# Channel_B.net
KiCad netlist of a schematic drawn in Altium Designer
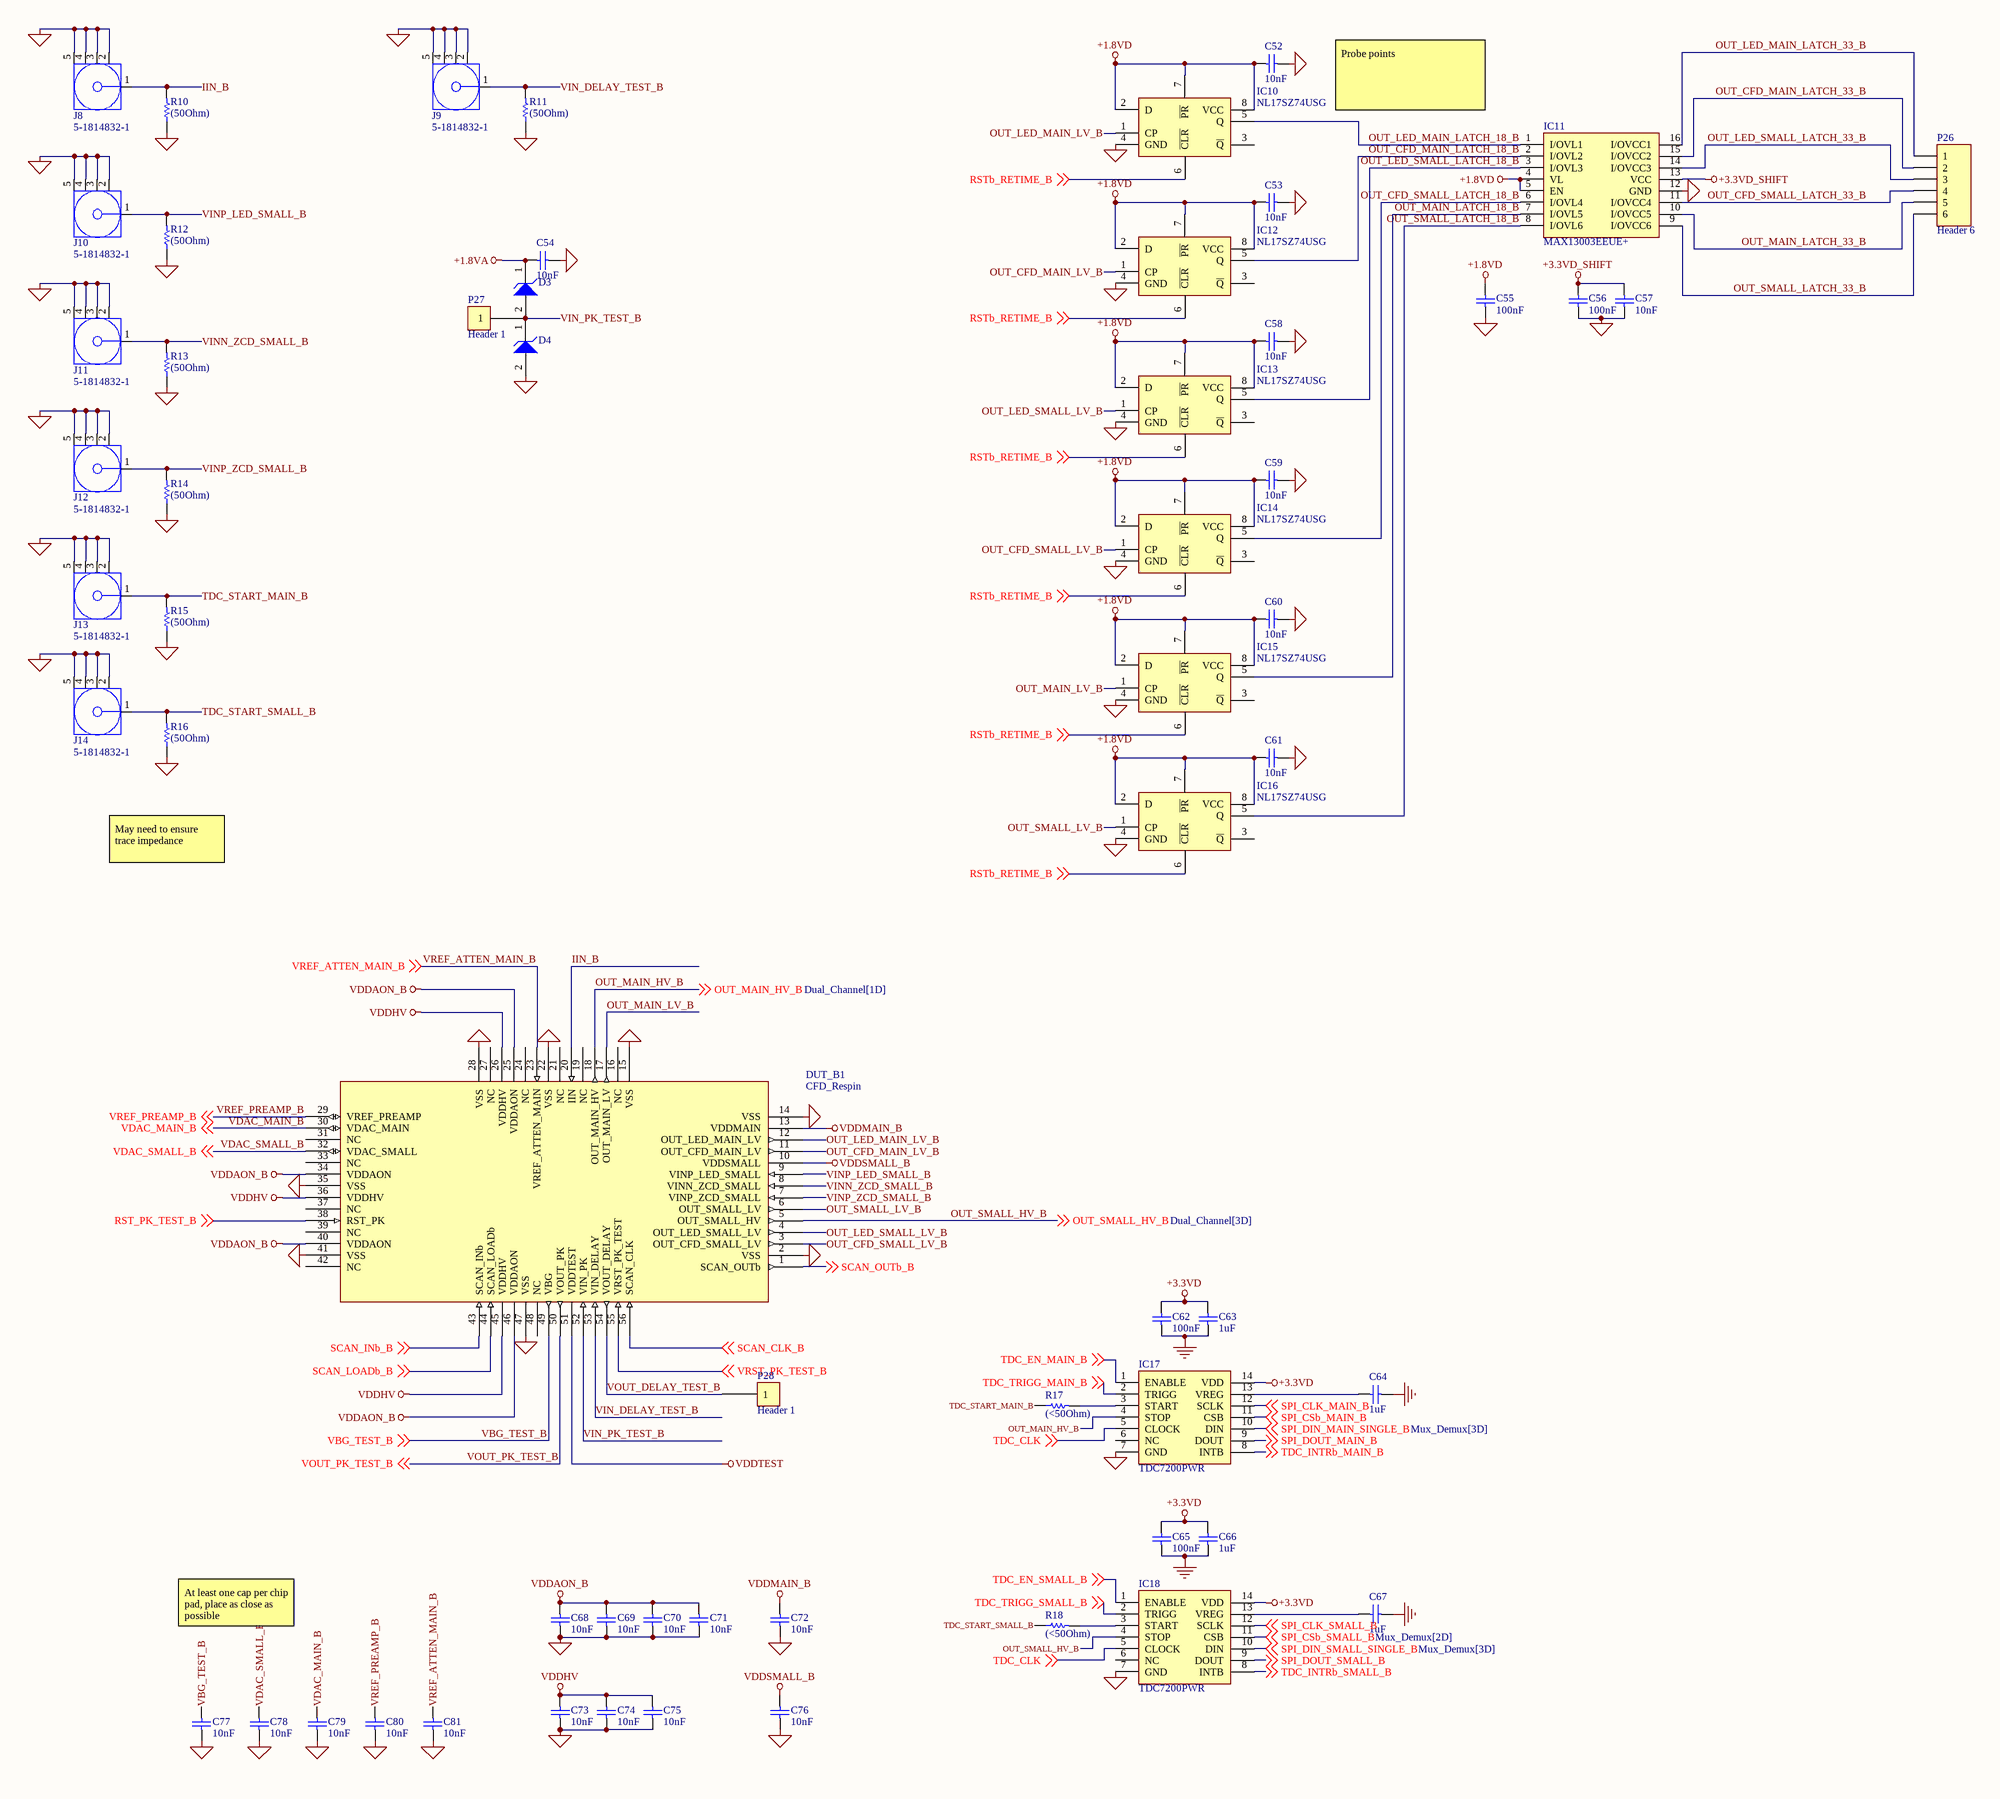
[diagram p0: Channel_B.SchDoc]

(export (version "E")
  (design (tool "Eeschema 10.0.6"))
  (components
    (comp (ref "C52")
      (value "10nF")
      (footprint "CAPC1608X90X35ML10T15")
      (description "0603")
      (fields (field (name "MANUFACTURER") "Murata"))
      (libsource (lib "Altium Content Vault") (part "CAP-NP-2"))
    )
    (comp (ref "C53")
      (value "10nF")
      (footprint "CAPC1608X90X35ML10T15")
      (description "0603")
      (fields (field (name "MANUFACTURER") "Murata"))
      (libsource (lib "Altium Content Vault") (part "CAP-NP-2"))
    )
    (comp (ref "C54")
      (value "10nF")
      (footprint "CAPC1608X90X35ML10T15")
      (description "0603")
      (fields (field (name "MANUFACTURER") "Murata"))
      (libsource (lib "Altium Content Vault") (part "CAP-NP-2"))
    )
    (comp (ref "C55")
      (value "100nF")
      (footprint "CAPC1608X90X35ML10T15")
      (description "0603")
      (fields (field (name "MANUFACTURER") "Murata"))
      (libsource (lib "Altium Content Vault") (part "CAP-NP-2"))
    )
    (comp (ref "C56")
      (value "100nF")
      (footprint "CAPC1608X90X35ML10T15")
      (description "0603")
      (fields (field (name "MANUFACTURER") "Murata"))
      (libsource (lib "Altium Content Vault") (part "CAP-NP-2"))
    )
    (comp (ref "C57")
      (value "10nF")
      (footprint "CAPC1608X90X35ML10T15")
      (description "0603")
      (fields (field (name "MANUFACTURER") "Murata"))
      (libsource (lib "Altium Content Vault") (part "CAP-NP-2"))
    )
    (comp (ref "C58")
      (value "10nF")
      (footprint "CAPC1608X90X35ML10T15")
      (description "0603")
      (fields (field (name "MANUFACTURER") "Murata"))
      (libsource (lib "Altium Content Vault") (part "CAP-NP-2"))
    )
    (comp (ref "C59")
      (value "10nF")
      (footprint "CAPC1608X90X35ML10T15")
      (description "0603")
      (fields (field (name "MANUFACTURER") "Murata"))
      (libsource (lib "Altium Content Vault") (part "CAP-NP-2"))
    )
    (comp (ref "C60")
      (value "10nF")
      (footprint "CAPC1608X90X35ML10T15")
      (description "0603")
      (fields (field (name "MANUFACTURER") "Murata"))
      (libsource (lib "Altium Content Vault") (part "CAP-NP-2"))
    )
    (comp (ref "C61")
      (value "10nF")
      (footprint "CAPC1608X90X35ML10T15")
      (description "0603")
      (fields (field (name "MANUFACTURER") "Murata"))
      (libsource (lib "Altium Content Vault") (part "CAP-NP-2"))
    )
    (comp (ref "C62")
      (value "100nF")
      (footprint "CAPC1608X90X35ML10T15")
      (description "0603")
      (fields (field (name "MANUFACTURER") "Murata"))
      (libsource (lib "Altium Content Vault") (part "CAP-NP-2"))
    )
    (comp (ref "C63")
      (value "1uF")
      (footprint "CAPC1608X90X35ML10T15")
      (description "0603")
      (fields (field (name "MANUFACTURER") "Murata"))
      (libsource (lib "Altium Content Vault") (part "CAP-NP-2"))
    )
    (comp (ref "C64")
      (value "1uF")
      (footprint "CAPC1608X90X35ML10T15")
      (description "0603")
      (fields (field (name "MANUFACTURER") "Murata"))
      (libsource (lib "Altium Content Vault") (part "CAP-NP-2"))
    )
    (comp (ref "C65")
      (value "100nF")
      (footprint "CAPC1608X90X35ML10T15")
      (description "0603")
      (fields (field (name "MANUFACTURER") "Murata"))
      (libsource (lib "Altium Content Vault") (part "CAP-NP-2"))
    )
    (comp (ref "C66")
      (value "1uF")
      (footprint "CAPC1608X90X35ML10T15")
      (description "0603")
      (fields (field (name "MANUFACTURER") "Murata"))
      (libsource (lib "Altium Content Vault") (part "CAP-NP-2"))
    )
    (comp (ref "C67")
      (value "1uF")
      (footprint "CAPC1608X90X35ML10T15")
      (description "0603")
      (fields (field (name "MANUFACTURER") "Murata"))
      (libsource (lib "Altium Content Vault") (part "CAP-NP-2"))
    )
    (comp (ref "C68")
      (value "10nF")
      (footprint "CAPC1608X90X35ML10T15")
      (description "0603")
      (fields (field (name "MANUFACTURER") "Murata"))
      (libsource (lib "Altium Content Vault") (part "CAP-NP-2"))
    )
    (comp (ref "C69")
      (value "10nF")
      (footprint "CAPC1608X90X35ML10T15")
      (description "0603")
      (fields (field (name "MANUFACTURER") "Murata"))
      (libsource (lib "Altium Content Vault") (part "CAP-NP-2"))
    )
    (comp (ref "C70")
      (value "10nF")
      (footprint "CAPC1608X90X35ML10T15")
      (description "0603")
      (fields (field (name "MANUFACTURER") "Murata"))
      (libsource (lib "Altium Content Vault") (part "CAP-NP-2"))
    )
    (comp (ref "C71")
      (value "10nF")
      (footprint "CAPC1608X90X35ML10T15")
      (description "0603")
      (fields (field (name "MANUFACTURER") "Murata"))
      (libsource (lib "Altium Content Vault") (part "CAP-NP-2"))
    )
    (comp (ref "C72")
      (value "10nF")
      (footprint "CAPC1608X90X35ML10T15")
      (description "0603")
      (fields (field (name "MANUFACTURER") "Murata"))
      (libsource (lib "Altium Content Vault") (part "CAP-NP-2"))
    )
    (comp (ref "C73")
      (value "10nF")
      (footprint "CAPC1608X90X35ML10T15")
      (description "0603")
      (fields (field (name "MANUFACTURER") "Murata"))
      (libsource (lib "Altium Content Vault") (part "CAP-NP-2"))
    )
    (comp (ref "C74")
      (value "10nF")
      (footprint "CAPC1608X90X35ML10T15")
      (description "0603")
      (fields (field (name "MANUFACTURER") "Murata"))
      (libsource (lib "Altium Content Vault") (part "CAP-NP-2"))
    )
    (comp (ref "C75")
      (value "10nF")
      (footprint "CAPC1608X90X35ML10T15")
      (description "0603")
      (fields (field (name "MANUFACTURER") "Murata"))
      (libsource (lib "Altium Content Vault") (part "CAP-NP-2"))
    )
    (comp (ref "C76")
      (value "10nF")
      (footprint "CAPC1608X90X35ML10T15")
      (description "0603")
      (fields (field (name "MANUFACTURER") "Murata"))
      (libsource (lib "Altium Content Vault") (part "CAP-NP-2"))
    )
    (comp (ref "C77")
      (value "10nF")
      (footprint "CAPC1608X90X35ML10T15")
      (description "0603")
      (fields (field (name "MANUFACTURER") "Murata"))
      (libsource (lib "Altium Content Vault") (part "CAP-NP-2"))
    )
    (comp (ref "C78")
      (value "10nF")
      (footprint "CAPC1608X90X35ML10T15")
      (description "0603")
      (fields (field (name "MANUFACTURER") "Murata"))
      (libsource (lib "Altium Content Vault") (part "CAP-NP-2"))
    )
    (comp (ref "C79")
      (value "10nF")
      (footprint "CAPC1608X90X35ML10T15")
      (description "0603")
      (fields (field (name "MANUFACTURER") "Murata"))
      (libsource (lib "Altium Content Vault") (part "CAP-NP-2"))
    )
    (comp (ref "C80")
      (value "10nF")
      (footprint "CAPC1608X90X35ML10T15")
      (description "0603")
      (fields (field (name "MANUFACTURER") "Murata"))
      (libsource (lib "Altium Content Vault") (part "CAP-NP-2"))
    )
    (comp (ref "C81")
      (value "10nF")
      (footprint "CAPC1608X90X35ML10T15")
      (description "0603")
      (fields (field (name "MANUFACTURER") "Murata"))
      (libsource (lib "Altium Content Vault") (part "CAP-NP-2"))
    )
    (comp (ref "D3")
      (value "~")
      (footprint "ONSC-SOD-123-2-425-04_V")
      (description "Zener Voltage Regulator, 2-Pin SOD-123, Pb-Free, Tape and Reel")
      (fields (field (name "MANUFACTURER") "On Semiconductor") (field (name "PARTNUMBER") "MMSZ4679T1G"))
      (libsource (lib "Altium Content Vault") (part "ONSC-K1A2-2"))
    )
    (comp (ref "D4")
      (value "~")
      (footprint "ONSC-SOD-123-2-425-04_V")
      (description "Zener Voltage Regulator, 2-Pin SOD-123, Pb-Free, Tape and Reel")
      (fields (field (name "MANUFACTURER") "On Semiconductor") (field (name "PARTNUMBER") "MMSZ4679T1G"))
      (libsource (lib "Altium Content Vault") (part "ONSC-K1A2-2"))
    )
    (comp (ref "DUT_B1")
      (value "CFD_Respin")
      (footprint "QFN50P800X800X80_HS-57N_WIDEVIAS")
      (libsource (lib "intlib") (part "CFD_Respin"))
    )
    (comp (ref "IC10")
      (value "NL17SZ74USG")
      (footprint "SamacSys:SOP50P310X90-8N")
      (description "Flip Flops 1.65-5.5V CMOS Single D-Type")
      (libsource (lib "SamacSys") (part "NL17SZ74USG"))
    )
    (comp (ref "IC11")
      (value "MAX13003EEUE+")
      (footprint "SamacSys:SOP65P640X110-16N")
      (description "Integrated Circuit")
      (libsource (lib "*") (part "MAX13003EEUE+"))
    )
    (comp (ref "IC12")
      (value "NL17SZ74USG")
      (footprint "SamacSys:SOP50P310X90-8N")
      (description "Flip Flops 1.65-5.5V CMOS Single D-Type")
      (libsource (lib "SamacSys") (part "NL17SZ74USG"))
    )
    (comp (ref "IC13")
      (value "NL17SZ74USG")
      (footprint "SamacSys:SOP50P310X90-8N")
      (description "Flip Flops 1.65-5.5V CMOS Single D-Type")
      (libsource (lib "SamacSys") (part "NL17SZ74USG"))
    )
    (comp (ref "IC14")
      (value "NL17SZ74USG")
      (footprint "SamacSys:SOP50P310X90-8N")
      (description "Flip Flops 1.65-5.5V CMOS Single D-Type")
      (libsource (lib "SamacSys") (part "NL17SZ74USG"))
    )
    (comp (ref "IC15")
      (value "NL17SZ74USG")
      (footprint "SamacSys:SOP50P310X90-8N")
      (description "Flip Flops 1.65-5.5V CMOS Single D-Type")
      (libsource (lib "SamacSys") (part "NL17SZ74USG"))
    )
    (comp (ref "IC16")
      (value "NL17SZ74USG")
      (footprint "SamacSys:SOP50P310X90-8N")
      (description "Flip Flops 1.65-5.5V CMOS Single D-Type")
      (libsource (lib "SamacSys") (part "NL17SZ74USG"))
    )
    (comp (ref "IC17")
      (value "TDC7200PWR")
      (footprint "SamacSys:SOP65P640X120-14N")
      (description "Integrated Circuit")
      (libsource (lib "*") (part "TDC7200PWR"))
    )
    (comp (ref "IC18")
      (value "TDC7200PWR")
      (footprint "SamacSys:SOP65P640X120-14N")
      (description "Integrated Circuit")
      (libsource (lib "*") (part "TDC7200PWR"))
    )
    (comp (ref "J8")
      (value "5-1814832-1")
      (footprint "TECO-5-1814832-1_V")
      (fields (field (name "MANUFACTURER") "TE Connectivity"))
      (libsource (lib "Altium Content Vault") (part "CN-S-4F-RF5"))
    )
    (comp (ref "J9")
      (value "5-1814832-1")
      (footprint "TECO-5-1814832-1_V")
      (fields (field (name "MANUFACTURER") "TE Connectivity"))
      (libsource (lib "Altium Content Vault") (part "CN-S-4F-RF5"))
    )
    (comp (ref "J10")
      (value "5-1814832-1")
      (footprint "TECO-5-1814832-1_V")
      (fields (field (name "MANUFACTURER") "TE Connectivity"))
      (libsource (lib "Altium Content Vault") (part "CN-S-4F-RF5"))
    )
    (comp (ref "J11")
      (value "5-1814832-1")
      (footprint "TECO-5-1814832-1_V")
      (fields (field (name "MANUFACTURER") "TE Connectivity"))
      (libsource (lib "Altium Content Vault") (part "CN-S-4F-RF5"))
    )
    (comp (ref "J12")
      (value "5-1814832-1")
      (footprint "TECO-5-1814832-1_V")
      (fields (field (name "MANUFACTURER") "TE Connectivity"))
      (libsource (lib "Altium Content Vault") (part "CN-S-4F-RF5"))
    )
    (comp (ref "J13")
      (value "5-1814832-1")
      (footprint "TECO-5-1814832-1_V")
      (fields (field (name "MANUFACTURER") "TE Connectivity"))
      (libsource (lib "Altium Content Vault") (part "CN-S-4F-RF5"))
    )
    (comp (ref "J14")
      (value "5-1814832-1")
      (footprint "TECO-5-1814832-1_V")
      (fields (field (name "MANUFACTURER") "TE Connectivity"))
      (libsource (lib "Altium Content Vault") (part "CN-S-4F-RF5"))
    )
    (comp (ref "P26")
      (value "Header 6")
      (footprint "HDR1X6")
      (description "Header, 6-Pin")
      (fields (field (name "PUBLISHER") "Altium Limited"))
      (libsource (lib "Miscellaneous Connectors") (part "Header 6"))
    )
    (comp (ref "P27") (value "Header 1") (footprint "Header1") (libsource (lib "intlib") (part "Header 1")))
    (comp (ref "P28") (value "Header 1") (footprint "Header1") (libsource (lib "") (part "Header 1_1")))
    (comp (ref "R10")
      (value "(50Ohm)")
      (footprint "RESC1609X50X30NL8T20")
      (description "0603")
      (fields (field (name "MANUFACTURER") "Vishay Semiconductor"))
      (libsource (lib "Altium Content Vault") (part "RES-2"))
    )
    (comp (ref "R11")
      (value "(50Ohm)")
      (footprint "RESC1609X50X30NL8T20")
      (description "0603")
      (fields (field (name "MANUFACTURER") "Vishay Semiconductor"))
      (libsource (lib "Altium Content Vault") (part "RES-2"))
    )
    (comp (ref "R12")
      (value "(50Ohm)")
      (footprint "RESC1609X50X30NL8T20")
      (description "0603")
      (fields (field (name "MANUFACTURER") "Vishay Semiconductor"))
      (libsource (lib "Altium Content Vault") (part "RES-2"))
    )
    (comp (ref "R13")
      (value "(50Ohm)")
      (footprint "RESC1609X50X30NL8T20")
      (description "0603")
      (fields (field (name "MANUFACTURER") "Vishay Semiconductor"))
      (libsource (lib "Altium Content Vault") (part "RES-2"))
    )
    (comp (ref "R14")
      (value "(50Ohm)")
      (footprint "RESC1609X50X30NL8T20")
      (description "0603")
      (fields (field (name "MANUFACTURER") "Vishay Semiconductor"))
      (libsource (lib "Altium Content Vault") (part "RES-2"))
    )
    (comp (ref "R15")
      (value "(50Ohm)")
      (footprint "RESC1609X50X30NL8T20")
      (description "0603")
      (fields (field (name "MANUFACTURER") "Vishay Semiconductor"))
      (libsource (lib "Altium Content Vault") (part "RES-2"))
    )
    (comp (ref "R16")
      (value "(50Ohm)")
      (footprint "RESC1609X50X30NL8T20")
      (description "0603")
      (fields (field (name "MANUFACTURER") "Vishay Semiconductor"))
      (libsource (lib "Altium Content Vault") (part "RES-2"))
    )
    (comp (ref "R17")
      (value "(<50Ohm)")
      (footprint "RESC1609X50X30NL8T20")
      (description "0603")
      (fields (field (name "MANUFACTURER") "Vishay Semiconductor"))
      (libsource (lib "Altium Content Vault") (part "RES-2"))
    )
    (comp (ref "R18")
      (value "(<50Ohm)")
      (footprint "RESC1609X50X30NL8T20")
      (description "0603")
      (fields (field (name "MANUFACTURER") "Vishay Semiconductor"))
      (libsource (lib "Altium Content Vault") (part "RES-2"))
    )
  )
  (nets
    (net (code "1") (name "+1.8VA") (class "Default")
      (node (ref "C54") (pin "2") (pinfunction "2_2") (pintype "passive"))
      (node (ref "D3") (pin "1") (pinfunction "K_1") (pintype "passive"))
    )
    (net (code "2") (name "+1.8VD") (class "Default")
      (node (ref "C52") (pin "2") (pinfunction "2_2") (pintype "passive"))
      (node (ref "C53") (pin "2") (pinfunction "2_2") (pintype "passive"))
      (node (ref "C55") (pin "2") (pinfunction "2_2") (pintype "passive"))
      (node (ref "C58") (pin "2") (pinfunction "2_2") (pintype "passive"))
      (node (ref "C59") (pin "2") (pinfunction "2_2") (pintype "passive"))
      (node (ref "C60") (pin "2") (pinfunction "2_2") (pintype "passive"))
      (node (ref "C61") (pin "2") (pinfunction "2_2") (pintype "passive"))
      (node (ref "IC10") (pin "2") (pinfunction "D_2") (pintype "passive"))
      (node (ref "IC10") (pin "7") (pinfunction "~{PR}_7") (pintype "passive"))
      (node (ref "IC10") (pin "8") (pinfunction "VCC_8") (pintype "passive"))
      (node (ref "IC11") (pin "4") (pinfunction "VL_4") (pintype "passive"))
      (node (ref "IC11") (pin "5") (pinfunction "EN_5") (pintype "passive"))
      (node (ref "IC12") (pin "2") (pinfunction "D_2") (pintype "passive"))
      (node (ref "IC12") (pin "7") (pinfunction "~{PR}_7") (pintype "passive"))
      (node (ref "IC12") (pin "8") (pinfunction "VCC_8") (pintype "passive"))
      (node (ref "IC13") (pin "2") (pinfunction "D_2") (pintype "passive"))
      (node (ref "IC13") (pin "7") (pinfunction "~{PR}_7") (pintype "passive"))
      (node (ref "IC13") (pin "8") (pinfunction "VCC_8") (pintype "passive"))
      (node (ref "IC14") (pin "2") (pinfunction "D_2") (pintype "passive"))
      (node (ref "IC14") (pin "7") (pinfunction "~{PR}_7") (pintype "passive"))
      (node (ref "IC14") (pin "8") (pinfunction "VCC_8") (pintype "passive"))
      (node (ref "IC15") (pin "2") (pinfunction "D_2") (pintype "passive"))
      (node (ref "IC15") (pin "7") (pinfunction "~{PR}_7") (pintype "passive"))
      (node (ref "IC15") (pin "8") (pinfunction "VCC_8") (pintype "passive"))
      (node (ref "IC16") (pin "2") (pinfunction "D_2") (pintype "passive"))
      (node (ref "IC16") (pin "7") (pinfunction "~{PR}_7") (pintype "passive"))
      (node (ref "IC16") (pin "8") (pinfunction "VCC_8") (pintype "passive"))
    )
    (net (code "3") (name "+3.3VD") (class "Default")
      (node (ref "C62") (pin "1") (pinfunction "1_1") (pintype "passive"))
      (node (ref "C63") (pin "1") (pinfunction "1_1") (pintype "passive"))
      (node (ref "C65") (pin "1") (pinfunction "1_1") (pintype "passive"))
      (node (ref "C66") (pin "1") (pinfunction "1_1") (pintype "passive"))
      (node (ref "IC17") (pin "14") (pinfunction "VDD_14") (pintype "passive"))
      (node (ref "IC18") (pin "14") (pinfunction "VDD_14") (pintype "passive"))
    )
    (net (code "4") (name "+3.3VD_SHIFT") (class "Default")
      (node (ref "C56") (pin "2") (pinfunction "2_2") (pintype "passive"))
      (node (ref "C57") (pin "2") (pinfunction "2_2") (pintype "passive"))
      (node (ref "IC11") (pin "13") (pinfunction "VCC_13") (pintype "passive"))
    )
    (net (code "5") (name "/IIN_B") (class "Default")
      (node (ref "DUT_B1") (pin "20") (pinfunction "IIN_20") (pintype "input"))
      (node (ref "J8") (pin "1") (pinfunction "1_1") (pintype "passive"))
      (node (ref "R10") (pin "2") (pinfunction "2_2") (pintype "passive"))
    )
    (net (code "6") (name "/OUT_CFD_MAIN_LATCH_18_B") (class "Default")
      (node (ref "IC11") (pin "2") (pinfunction "I/OVL2_2") (pintype "passive"))
      (node (ref "IC12") (pin "5") (pinfunction "Q_5") (pintype "passive"))
    )
    (net (code "7") (name "/OUT_CFD_MAIN_LATCH_33_B") (class "Default")
      (node (ref "IC11") (pin "15") (pinfunction "I/OVCC2_15") (pintype "passive"))
      (node (ref "P26") (pin "2") (pinfunction "2_2") (pintype "passive"))
    )
    (net (code "8") (name "/OUT_CFD_MAIN_LV_B") (class "Default")
      (node (ref "DUT_B1") (pin "11") (pinfunction "OUT_CFD_MAIN_LV_11") (pintype "output"))
      (node (ref "IC12") (pin "1") (pinfunction "CP_1") (pintype "passive"))
    )
    (net (code "9") (name "/OUT_CFD_SMALL_LATCH_18_B") (class "Default")
      (node (ref "IC11") (pin "6") (pinfunction "I/OVL4_6") (pintype "passive"))
      (node (ref "IC14") (pin "5") (pinfunction "Q_5") (pintype "passive"))
    )
    (net (code "10") (name "/OUT_CFD_SMALL_LATCH_33_B") (class "Default")
      (node (ref "IC11") (pin "11") (pinfunction "I/OVCC4_11") (pintype "passive"))
      (node (ref "P26") (pin "4") (pinfunction "4_4") (pintype "passive"))
    )
    (net (code "11") (name "/OUT_CFD_SMALL_LV_B") (class "Default")
      (node (ref "DUT_B1") (pin "3") (pinfunction "OUT_CFD_SMALL_LV_3") (pintype "output"))
      (node (ref "IC14") (pin "1") (pinfunction "CP_1") (pintype "passive"))
    )
    (net (code "12") (name "/OUT_LED_MAIN_LATCH_18_B") (class "Default")
      (node (ref "IC10") (pin "5") (pinfunction "Q_5") (pintype "passive"))
      (node (ref "IC11") (pin "1") (pinfunction "I/OVL1_1") (pintype "passive"))
    )
    (net (code "13") (name "/OUT_LED_MAIN_LATCH_33_B") (class "Default")
      (node (ref "IC11") (pin "16") (pinfunction "I/OVCC1_16") (pintype "passive"))
      (node (ref "P26") (pin "1") (pinfunction "1_1") (pintype "passive"))
    )
    (net (code "14") (name "/OUT_LED_MAIN_LV_B") (class "Default")
      (node (ref "DUT_B1") (pin "12") (pinfunction "OUT_LED_MAIN_LV_12") (pintype "output"))
      (node (ref "IC10") (pin "1") (pinfunction "CP_1") (pintype "passive"))
    )
    (net (code "15") (name "/OUT_LED_SMALL_LATCH_18_B") (class "Default")
      (node (ref "IC11") (pin "3") (pinfunction "I/OVL3_3") (pintype "passive"))
      (node (ref "IC13") (pin "5") (pinfunction "Q_5") (pintype "passive"))
    )
    (net (code "16") (name "/OUT_LED_SMALL_LATCH_33_B") (class "Default")
      (node (ref "IC11") (pin "14") (pinfunction "I/OVCC3_14") (pintype "passive"))
      (node (ref "P26") (pin "3") (pinfunction "3_3") (pintype "passive"))
    )
    (net (code "17") (name "/OUT_LED_SMALL_LV_B") (class "Default")
      (node (ref "DUT_B1") (pin "4") (pinfunction "OUT_LED_SMALL_LV_4") (pintype "output"))
      (node (ref "IC13") (pin "1") (pinfunction "CP_1") (pintype "passive"))
    )
    (net (code "18") (name "/OUT_MAIN_LATCH_18_B") (class "Default")
      (node (ref "IC11") (pin "7") (pinfunction "I/OVL5_7") (pintype "passive"))
      (node (ref "IC15") (pin "5") (pinfunction "Q_5") (pintype "passive"))
    )
    (net (code "19") (name "/OUT_MAIN_LATCH_33_B") (class "Default")
      (node (ref "IC11") (pin "10") (pinfunction "I/OVCC5_10") (pintype "passive"))
      (node (ref "P26") (pin "5") (pinfunction "5_5") (pintype "passive"))
    )
    (net (code "20") (name "/OUT_MAIN_LV_B") (class "Default")
      (node (ref "DUT_B1") (pin "17") (pinfunction "OUT_MAIN_LV_17") (pintype "output"))
      (node (ref "IC15") (pin "1") (pinfunction "CP_1") (pintype "passive"))
    )
    (net (code "21") (name "/OUT_SMALL_LATCH_18_B") (class "Default")
      (node (ref "IC11") (pin "8") (pinfunction "I/OVL6_8") (pintype "passive"))
      (node (ref "IC16") (pin "5") (pinfunction "Q_5") (pintype "passive"))
    )
    (net (code "22") (name "/OUT_SMALL_LATCH_33_B") (class "Default")
      (node (ref "IC11") (pin "9") (pinfunction "I/OVCC6_9") (pintype "passive"))
      (node (ref "P26") (pin "6") (pinfunction "6_6") (pintype "passive"))
    )
    (net (code "23") (name "/OUT_SMALL_LV_B") (class "Default")
      (node (ref "DUT_B1") (pin "6") (pinfunction "OUT_SMALL_LV_6") (pintype "output"))
      (node (ref "IC16") (pin "1") (pinfunction "CP_1") (pintype "passive"))
    )
    (net (code "24") (name "/TDC_START_MAIN_B") (class "Default")
      (node (ref "J13") (pin "1") (pinfunction "1_1") (pintype "passive"))
      (node (ref "R15") (pin "2") (pinfunction "2_2") (pintype "passive"))
      (node (ref "R17") (pin "1") (pinfunction "1_1") (pintype "passive"))
    )
    (net (code "25") (name "/TDC_START_SMALL_B") (class "Default")
      (node (ref "J14") (pin "1") (pinfunction "1_1") (pintype "passive"))
      (node (ref "R16") (pin "2") (pinfunction "2_2") (pintype "passive"))
      (node (ref "R18") (pin "1") (pinfunction "1_1") (pintype "passive"))
    )
    (net (code "26") (name "/VINN_ZCD_SMALL_B") (class "Default")
      (node (ref "DUT_B1") (pin "8") (pinfunction "VINN_ZCD_SMALL_8") (pintype "input"))
      (node (ref "J11") (pin "1") (pinfunction "1_1") (pintype "passive"))
      (node (ref "R13") (pin "2") (pinfunction "2_2") (pintype "passive"))
    )
    (net (code "27") (name "/VINP_LED_SMALL_B") (class "Default")
      (node (ref "DUT_B1") (pin "9") (pinfunction "VINP_LED_SMALL_9") (pintype "input"))
      (node (ref "J10") (pin "1") (pinfunction "1_1") (pintype "passive"))
      (node (ref "R12") (pin "2") (pinfunction "2_2") (pintype "passive"))
    )
    (net (code "28") (name "/VINP_ZCD_SMALL_B") (class "Default")
      (node (ref "DUT_B1") (pin "7") (pinfunction "VINP_ZCD_SMALL_7") (pintype "input"))
      (node (ref "J12") (pin "1") (pinfunction "1_1") (pintype "passive"))
      (node (ref "R14") (pin "2") (pinfunction "2_2") (pintype "passive"))
    )
    (net (code "29") (name "/VIN_DELAY_TEST_B") (class "Default")
      (node (ref "DUT_B1") (pin "53") (pinfunction "VIN_DELAY_53") (pintype "input"))
      (node (ref "J9") (pin "1") (pinfunction "1_1") (pintype "passive"))
      (node (ref "R11") (pin "2") (pinfunction "2_2") (pintype "passive"))
    )
    (net (code "30") (name "/VIN_PK_TEST_B") (class "Default")
      (node (ref "D3") (pin "2") (pinfunction "A_2") (pintype "passive"))
      (node (ref "D4") (pin "1") (pinfunction "K_1") (pintype "passive"))
      (node (ref "DUT_B1") (pin "52") (pinfunction "VIN_PK_52") (pintype "input"))
      (node (ref "P27") (pin "1") (pinfunction "1_1") (pintype "passive"))
    )
    (net (code "31") (name "/VOUT_DELAY_TEST_B") (class "Default")
      (node (ref "DUT_B1") (pin "54") (pinfunction "VOUT_DELAY_54") (pintype "output"))
      (node (ref "P28") (pin "1") (pinfunction "1_1") (pintype "passive"))
    )
    (net (code "32") (name "GND") (class "Default")
      (node (ref "C52") (pin "1") (pinfunction "1_1") (pintype "passive"))
      (node (ref "C53") (pin "1") (pinfunction "1_1") (pintype "passive"))
      (node (ref "C54") (pin "1") (pinfunction "1_1") (pintype "passive"))
      (node (ref "C55") (pin "1") (pinfunction "1_1") (pintype "passive"))
      (node (ref "C56") (pin "1") (pinfunction "1_1") (pintype "passive"))
      (node (ref "C57") (pin "1") (pinfunction "1_1") (pintype "passive"))
      (node (ref "C58") (pin "1") (pinfunction "1_1") (pintype "passive"))
      (node (ref "C59") (pin "1") (pinfunction "1_1") (pintype "passive"))
      (node (ref "C60") (pin "1") (pinfunction "1_1") (pintype "passive"))
      (node (ref "C61") (pin "1") (pinfunction "1_1") (pintype "passive"))
      (node (ref "C62") (pin "2") (pinfunction "2_2") (pintype "passive"))
      (node (ref "C63") (pin "2") (pinfunction "2_2") (pintype "passive"))
      (node (ref "C64") (pin "2") (pinfunction "2_2") (pintype "passive"))
      (node (ref "C65") (pin "2") (pinfunction "2_2") (pintype "passive"))
      (node (ref "C66") (pin "2") (pinfunction "2_2") (pintype "passive"))
      (node (ref "C67") (pin "2") (pinfunction "2_2") (pintype "passive"))
      (node (ref "C68") (pin "1") (pinfunction "1_1") (pintype "passive"))
      (node (ref "C69") (pin "1") (pinfunction "1_1") (pintype "passive"))
      (node (ref "C70") (pin "1") (pinfunction "1_1") (pintype "passive"))
      (node (ref "C71") (pin "1") (pinfunction "1_1") (pintype "passive"))
      (node (ref "C72") (pin "1") (pinfunction "1_1") (pintype "passive"))
      (node (ref "C73") (pin "1") (pinfunction "1_1") (pintype "passive"))
      (node (ref "C74") (pin "1") (pinfunction "1_1") (pintype "passive"))
      (node (ref "C75") (pin "1") (pinfunction "1_1") (pintype "passive"))
      (node (ref "C76") (pin "1") (pinfunction "1_1") (pintype "passive"))
      (node (ref "C77") (pin "1") (pinfunction "1_1") (pintype "passive"))
      (node (ref "C78") (pin "1") (pinfunction "1_1") (pintype "passive"))
      (node (ref "C79") (pin "1") (pinfunction "1_1") (pintype "passive"))
      (node (ref "C80") (pin "1") (pinfunction "1_1") (pintype "passive"))
      (node (ref "C81") (pin "1") (pinfunction "1_1") (pintype "passive"))
      (node (ref "D4") (pin "2") (pinfunction "A_2") (pintype "passive"))
      (node (ref "DUT_B1") (pin "14") (pinfunction "VSS_14") (pintype "power_in"))
      (node (ref "DUT_B1") (pin "15") (pinfunction "VSS_15") (pintype "power_in"))
      (node (ref "DUT_B1") (pin "2") (pinfunction "VSS_2") (pintype "power_in"))
      (node (ref "DUT_B1") (pin "22") (pinfunction "VSS_22") (pintype "power_in"))
      (node (ref "DUT_B1") (pin "28") (pinfunction "VSS_28") (pintype "power_in"))
      (node (ref "DUT_B1") (pin "35") (pinfunction "VSS_35") (pintype "power_in"))
      (node (ref "DUT_B1") (pin "41") (pinfunction "VSS_41") (pintype "power_in"))
      (node (ref "DUT_B1") (pin "47") (pinfunction "VSS_47") (pintype "power_in"))
      (node (ref "IC10") (pin "4") (pinfunction "GND_4") (pintype "passive"))
      (node (ref "IC11") (pin "12") (pinfunction "GND_12") (pintype "passive"))
      (node (ref "IC12") (pin "4") (pinfunction "GND_4") (pintype "passive"))
      (node (ref "IC13") (pin "4") (pinfunction "GND_4") (pintype "passive"))
      (node (ref "IC14") (pin "4") (pinfunction "GND_4") (pintype "passive"))
      (node (ref "IC15") (pin "4") (pinfunction "GND_4") (pintype "passive"))
      (node (ref "IC16") (pin "4") (pinfunction "GND_4") (pintype "passive"))
      (node (ref "IC17") (pin "7") (pinfunction "GND_7") (pintype "passive"))
      (node (ref "IC18") (pin "7") (pinfunction "GND_7") (pintype "passive"))
      (node (ref "J10") (pin "2") (pinfunction "2_2") (pintype "passive"))
      (node (ref "J10") (pin "3") (pinfunction "3_3") (pintype "passive"))
      (node (ref "J10") (pin "4") (pinfunction "4_4") (pintype "passive"))
      (node (ref "J10") (pin "5") (pinfunction "5_5") (pintype "passive"))
      (node (ref "J11") (pin "2") (pinfunction "2_2") (pintype "passive"))
      (node (ref "J11") (pin "3") (pinfunction "3_3") (pintype "passive"))
      (node (ref "J11") (pin "4") (pinfunction "4_4") (pintype "passive"))
      (node (ref "J11") (pin "5") (pinfunction "5_5") (pintype "passive"))
      (node (ref "J12") (pin "2") (pinfunction "2_2") (pintype "passive"))
      (node (ref "J12") (pin "3") (pinfunction "3_3") (pintype "passive"))
      (node (ref "J12") (pin "4") (pinfunction "4_4") (pintype "passive"))
      (node (ref "J12") (pin "5") (pinfunction "5_5") (pintype "passive"))
      (node (ref "J13") (pin "2") (pinfunction "2_2") (pintype "passive"))
      (node (ref "J13") (pin "3") (pinfunction "3_3") (pintype "passive"))
      (node (ref "J13") (pin "4") (pinfunction "4_4") (pintype "passive"))
      (node (ref "J13") (pin "5") (pinfunction "5_5") (pintype "passive"))
      (node (ref "J14") (pin "2") (pinfunction "2_2") (pintype "passive"))
      (node (ref "J14") (pin "3") (pinfunction "3_3") (pintype "passive"))
      (node (ref "J14") (pin "4") (pinfunction "4_4") (pintype "passive"))
      (node (ref "J14") (pin "5") (pinfunction "5_5") (pintype "passive"))
      (node (ref "J8") (pin "2") (pinfunction "2_2") (pintype "passive"))
      (node (ref "J8") (pin "3") (pinfunction "3_3") (pintype "passive"))
      (node (ref "J8") (pin "4") (pinfunction "4_4") (pintype "passive"))
      (node (ref "J8") (pin "5") (pinfunction "5_5") (pintype "passive"))
      (node (ref "J9") (pin "2") (pinfunction "2_2") (pintype "passive"))
      (node (ref "J9") (pin "3") (pinfunction "3_3") (pintype "passive"))
      (node (ref "J9") (pin "4") (pinfunction "4_4") (pintype "passive"))
      (node (ref "J9") (pin "5") (pinfunction "5_5") (pintype "passive"))
      (node (ref "R10") (pin "1") (pinfunction "1_1") (pintype "passive"))
      (node (ref "R11") (pin "1") (pinfunction "1_1") (pintype "passive"))
      (node (ref "R12") (pin "1") (pinfunction "1_1") (pintype "passive"))
      (node (ref "R13") (pin "1") (pinfunction "1_1") (pintype "passive"))
      (node (ref "R14") (pin "1") (pinfunction "1_1") (pintype "passive"))
      (node (ref "R15") (pin "1") (pinfunction "1_1") (pintype "passive"))
      (node (ref "R16") (pin "1") (pinfunction "1_1") (pintype "passive"))
    )
    (net (code "33") (name "Net-(IC17-START)") (class "Default")
      (node (ref "IC17") (pin "3") (pinfunction "START_3") (pintype "passive"))
      (node (ref "R17") (pin "2") (pinfunction "2_2") (pintype "passive"))
    )
    (net (code "34") (name "Net-(IC17-VREG)") (class "Default")
      (node (ref "C64") (pin "1") (pinfunction "1_1") (pintype "passive"))
      (node (ref "IC17") (pin "13") (pinfunction "VREG_13") (pintype "passive"))
    )
    (net (code "35") (name "Net-(IC18-START)") (class "Default")
      (node (ref "IC18") (pin "3") (pinfunction "START_3") (pintype "passive"))
      (node (ref "R18") (pin "2") (pinfunction "2_2") (pintype "passive"))
    )
    (net (code "36") (name "Net-(IC18-VREG)") (class "Default")
      (node (ref "C67") (pin "1") (pinfunction "1_1") (pintype "passive"))
      (node (ref "IC18") (pin "13") (pinfunction "VREG_13") (pintype "passive"))
    )
    (net (code "37") (name "OUT_MAIN_HV_B") (class "Default")
      (node (ref "DUT_B1") (pin "18") (pinfunction "OUT_MAIN_HV_18") (pintype "output"))
      (node (ref "IC17") (pin "4") (pinfunction "STOP_4") (pintype "passive"))
    )
    (net (code "38") (name "OUT_SMALL_HV_B") (class "Default")
      (node (ref "DUT_B1") (pin "5") (pinfunction "OUT_SMALL_HV_5") (pintype "output"))
      (node (ref "IC18") (pin "4") (pinfunction "STOP_4") (pintype "passive"))
    )
    (net (code "39") (name "RST_PK_TEST_B") (class "Default")
      (node (ref "DUT_B1") (pin "38") (pinfunction "RST_PK_38") (pintype "input"))
    )
    (net (code "40") (name "RSTb_RETIME_B") (class "Default")
      (node (ref "IC10") (pin "6") (pinfunction "~{CLR}_6") (pintype "passive"))
      (node (ref "IC12") (pin "6") (pinfunction "~{CLR}_6") (pintype "passive"))
      (node (ref "IC13") (pin "6") (pinfunction "~{CLR}_6") (pintype "passive"))
      (node (ref "IC14") (pin "6") (pinfunction "~{CLR}_6") (pintype "passive"))
      (node (ref "IC15") (pin "6") (pinfunction "~{CLR}_6") (pintype "passive"))
      (node (ref "IC16") (pin "6") (pinfunction "~{CLR}_6") (pintype "passive"))
    )
    (net (code "41") (name "SCAN_CLK_B") (class "Default")
      (node (ref "DUT_B1") (pin "56") (pinfunction "SCAN_CLK_56") (pintype "input"))
    )
    (net (code "42") (name "SCAN_INb_B") (class "Default")
      (node (ref "DUT_B1") (pin "43") (pinfunction "SCAN_INb_43") (pintype "input"))
    )
    (net (code "43") (name "SCAN_LOADb_B") (class "Default")
      (node (ref "DUT_B1") (pin "44") (pinfunction "SCAN_LOADb_44") (pintype "input"))
    )
    (net (code "44") (name "SCAN_OUTb_B") (class "Default")
      (node (ref "DUT_B1") (pin "1") (pinfunction "SCAN_OUTb_1") (pintype "output"))
    )
    (net (code "45") (name "SPI_CLK_MAIN_B") (class "Default")
      (node (ref "IC17") (pin "12") (pinfunction "SCLK_12") (pintype "passive"))
    )
    (net (code "46") (name "SPI_CLK_SMALL_B") (class "Default")
      (node (ref "IC18") (pin "12") (pinfunction "SCLK_12") (pintype "passive"))
    )
    (net (code "47") (name "SPI_CSb_MAIN_B") (class "Default")
      (node (ref "IC17") (pin "11") (pinfunction "CSB_11") (pintype "passive"))
    )
    (net (code "48") (name "SPI_CSb_SMALL_B") (class "Default")
      (node (ref "IC18") (pin "11") (pinfunction "CSB_11") (pintype "passive"))
    )
    (net (code "49") (name "SPI_DIN_MAIN_SINGLE_B") (class "Default")
      (node (ref "IC17") (pin "10") (pinfunction "DIN_10") (pintype "passive"))
    )
    (net (code "50") (name "SPI_DIN_SMALL_SINGLE_B") (class "Default")
      (node (ref "IC18") (pin "10") (pinfunction "DIN_10") (pintype "passive"))
    )
    (net (code "51") (name "SPI_DOUT_MAIN_B") (class "Default")
      (node (ref "IC17") (pin "9") (pinfunction "DOUT_9") (pintype "passive"))
    )
    (net (code "52") (name "SPI_DOUT_SMALL_B") (class "Default")
      (node (ref "IC18") (pin "9") (pinfunction "DOUT_9") (pintype "passive"))
    )
    (net (code "53") (name "TDC_CLK") (class "Default")
      (node (ref "IC17") (pin "5") (pinfunction "CLOCK_5") (pintype "passive"))
      (node (ref "IC18") (pin "5") (pinfunction "CLOCK_5") (pintype "passive"))
    )
    (net (code "54") (name "TDC_EN_MAIN_B") (class "Default")
      (node (ref "IC17") (pin "1") (pinfunction "ENABLE_1") (pintype "passive"))
    )
    (net (code "55") (name "TDC_EN_SMALL_B") (class "Default")
      (node (ref "IC18") (pin "1") (pinfunction "ENABLE_1") (pintype "passive"))
    )
    (net (code "56") (name "TDC_INTRb_MAIN_B") (class "Default")
      (node (ref "IC17") (pin "8") (pinfunction "INTB_8") (pintype "passive"))
    )
    (net (code "57") (name "TDC_INTRb_SMALL_B") (class "Default")
      (node (ref "IC18") (pin "8") (pinfunction "INTB_8") (pintype "passive"))
    )
    (net (code "58") (name "TDC_TRIGG_MAIN_B") (class "Default")
      (node (ref "IC17") (pin "2") (pinfunction "TRIGG_2") (pintype "passive"))
    )
    (net (code "59") (name "TDC_TRIGG_SMALL_B") (class "Default")
      (node (ref "IC18") (pin "2") (pinfunction "TRIGG_2") (pintype "passive"))
    )
    (net (code "60") (name "VBG_TEST_B") (class "Default")
      (node (ref "C77") (pin "2") (pinfunction "2_2") (pintype "passive"))
      (node (ref "DUT_B1") (pin "49") (pinfunction "VBG_49") (pintype "output"))
    )
    (net (code "61") (name "VDAC_MAIN_B") (class "Default")
      (node (ref "C79") (pin "2") (pinfunction "2_2") (pintype "passive"))
      (node (ref "DUT_B1") (pin "30") (pinfunction "VDAC_MAIN_30") (pintype "bidirectional"))
    )
    (net (code "62") (name "VDAC_SMALL_B") (class "Default")
      (node (ref "C78") (pin "2") (pinfunction "2_2") (pintype "passive"))
      (node (ref "DUT_B1") (pin "32") (pinfunction "VDAC_SMALL_32") (pintype "bidirectional"))
    )
    (net (code "63") (name "VDDAON_B") (class "Default")
      (node (ref "C68") (pin "2") (pinfunction "2_2") (pintype "passive"))
      (node (ref "C69") (pin "2") (pinfunction "2_2") (pintype "passive"))
      (node (ref "C70") (pin "2") (pinfunction "2_2") (pintype "passive"))
      (node (ref "C71") (pin "2") (pinfunction "2_2") (pintype "passive"))
      (node (ref "DUT_B1") (pin "25") (pinfunction "VDDAON_25") (pintype "power_in"))
      (node (ref "DUT_B1") (pin "34") (pinfunction "VDDAON_34") (pintype "power_in"))
      (node (ref "DUT_B1") (pin "40") (pinfunction "VDDAON_40") (pintype "power_in"))
      (node (ref "DUT_B1") (pin "46") (pinfunction "VDDAON_46") (pintype "power_in"))
    )
    (net (code "64") (name "VDDHV") (class "Default")
      (node (ref "C73") (pin "2") (pinfunction "2_2") (pintype "passive"))
      (node (ref "C74") (pin "2") (pinfunction "2_2") (pintype "passive"))
      (node (ref "C75") (pin "2") (pinfunction "2_2") (pintype "passive"))
      (node (ref "DUT_B1") (pin "26") (pinfunction "VDDHV_26") (pintype "power_in"))
      (node (ref "DUT_B1") (pin "36") (pinfunction "VDDHV_36") (pintype "power_in"))
      (node (ref "DUT_B1") (pin "45") (pinfunction "VDDHV_45") (pintype "power_in"))
    )
    (net (code "65") (name "VDDMAIN_B") (class "Default")
      (node (ref "C72") (pin "2") (pinfunction "2_2") (pintype "passive"))
      (node (ref "DUT_B1") (pin "13") (pinfunction "VDDMAIN_13") (pintype "power_in"))
    )
    (net (code "66") (name "VDDSMALL_B") (class "Default")
      (node (ref "C76") (pin "2") (pinfunction "2_2") (pintype "passive"))
      (node (ref "DUT_B1") (pin "10") (pinfunction "VDDSMALL_10") (pintype "power_in"))
    )
    (net (code "67") (name "VDDTEST") (class "Default")
      (node (ref "DUT_B1") (pin "51") (pinfunction "VDDTEST_51") (pintype "power_in"))
    )
    (net (code "68") (name "VOUT_PK_TEST_B") (class "Default")
      (node (ref "DUT_B1") (pin "50") (pinfunction "VOUT_PK_50") (pintype "output"))
    )
    (net (code "69") (name "VREF_ATTEN_MAIN_B") (class "Default")
      (node (ref "C81") (pin "2") (pinfunction "2_2") (pintype "passive"))
      (node (ref "DUT_B1") (pin "23") (pinfunction "VREF_ATTEN_MAIN_23") (pintype "input"))
    )
    (net (code "70") (name "VREF_PREAMP_B") (class "Default")
      (node (ref "C80") (pin "2") (pinfunction "2_2") (pintype "passive"))
      (node (ref "DUT_B1") (pin "29") (pinfunction "VREF_PREAMP_29") (pintype "bidirectional"))
    )
    (net (code "71") (name "VRST_PK_TEST_B") (class "Default")
      (node (ref "DUT_B1") (pin "55") (pinfunction "VRST_PK_TEST_55") (pintype "input"))
    )
    (net (code "72") (name "unconnected-(DUT_B1-NC-Pad16)") (class "Default")
      (node (ref "DUT_B1") (pin "16") (pinfunction "NC_16") (pintype "passive"))
    )
    (net (code "73") (name "unconnected-(DUT_B1-NC-Pad19)") (class "Default")
      (node (ref "DUT_B1") (pin "19") (pinfunction "NC_19") (pintype "passive"))
    )
    (net (code "74") (name "unconnected-(DUT_B1-NC-Pad21)") (class "Default")
      (node (ref "DUT_B1") (pin "21") (pinfunction "NC_21") (pintype "passive"))
    )
    (net (code "75") (name "unconnected-(DUT_B1-NC-Pad24)") (class "Default")
      (node (ref "DUT_B1") (pin "24") (pinfunction "NC_24") (pintype "passive"))
    )
    (net (code "76") (name "unconnected-(DUT_B1-NC-Pad27)") (class "Default")
      (node (ref "DUT_B1") (pin "27") (pinfunction "NC_27") (pintype "passive"))
    )
    (net (code "77") (name "unconnected-(DUT_B1-NC-Pad31)") (class "Default")
      (node (ref "DUT_B1") (pin "31") (pinfunction "NC_31") (pintype "passive"))
    )
    (net (code "78") (name "unconnected-(DUT_B1-NC-Pad33)") (class "Default")
      (node (ref "DUT_B1") (pin "33") (pinfunction "NC_33") (pintype "passive"))
    )
    (net (code "79") (name "unconnected-(DUT_B1-NC-Pad37)") (class "Default")
      (node (ref "DUT_B1") (pin "37") (pinfunction "NC_37") (pintype "passive"))
    )
    (net (code "80") (name "unconnected-(DUT_B1-NC-Pad39)") (class "Default")
      (node (ref "DUT_B1") (pin "39") (pinfunction "NC_39") (pintype "passive"))
    )
    (net (code "81") (name "unconnected-(DUT_B1-NC-Pad42)") (class "Default")
      (node (ref "DUT_B1") (pin "42") (pinfunction "NC_42") (pintype "passive"))
    )
    (net (code "82") (name "unconnected-(DUT_B1-NC-Pad48)") (class "Default")
      (node (ref "DUT_B1") (pin "48") (pinfunction "NC_48") (pintype "passive"))
    )
    (net (code "83") (name "unconnected-(IC10-~{Q}-Pad3)") (class "Default")
      (node (ref "IC10") (pin "3") (pinfunction "~{Q}_3") (pintype "passive"))
    )
    (net (code "84") (name "unconnected-(IC12-~{Q}-Pad3)") (class "Default")
      (node (ref "IC12") (pin "3") (pinfunction "~{Q}_3") (pintype "passive"))
    )
    (net (code "85") (name "unconnected-(IC13-~{Q}-Pad3)") (class "Default")
      (node (ref "IC13") (pin "3") (pinfunction "~{Q}_3") (pintype "passive"))
    )
    (net (code "86") (name "unconnected-(IC14-~{Q}-Pad3)") (class "Default")
      (node (ref "IC14") (pin "3") (pinfunction "~{Q}_3") (pintype "passive"))
    )
    (net (code "87") (name "unconnected-(IC15-~{Q}-Pad3)") (class "Default")
      (node (ref "IC15") (pin "3") (pinfunction "~{Q}_3") (pintype "passive"))
    )
    (net (code "88") (name "unconnected-(IC16-~{Q}-Pad3)") (class "Default")
      (node (ref "IC16") (pin "3") (pinfunction "~{Q}_3") (pintype "passive"))
    )
    (net (code "89") (name "unconnected-(IC17-NC-Pad6)") (class "Default")
      (node (ref "IC17") (pin "6") (pinfunction "NC_6") (pintype "passive"))
    )
    (net (code "90") (name "unconnected-(IC18-NC-Pad6)") (class "Default")
      (node (ref "IC18") (pin "6") (pinfunction "NC_6") (pintype "passive"))
    )
  )
)
